# ArduinoPCB_test.net
KiCad netlist of a schematic drawn in EAGLE
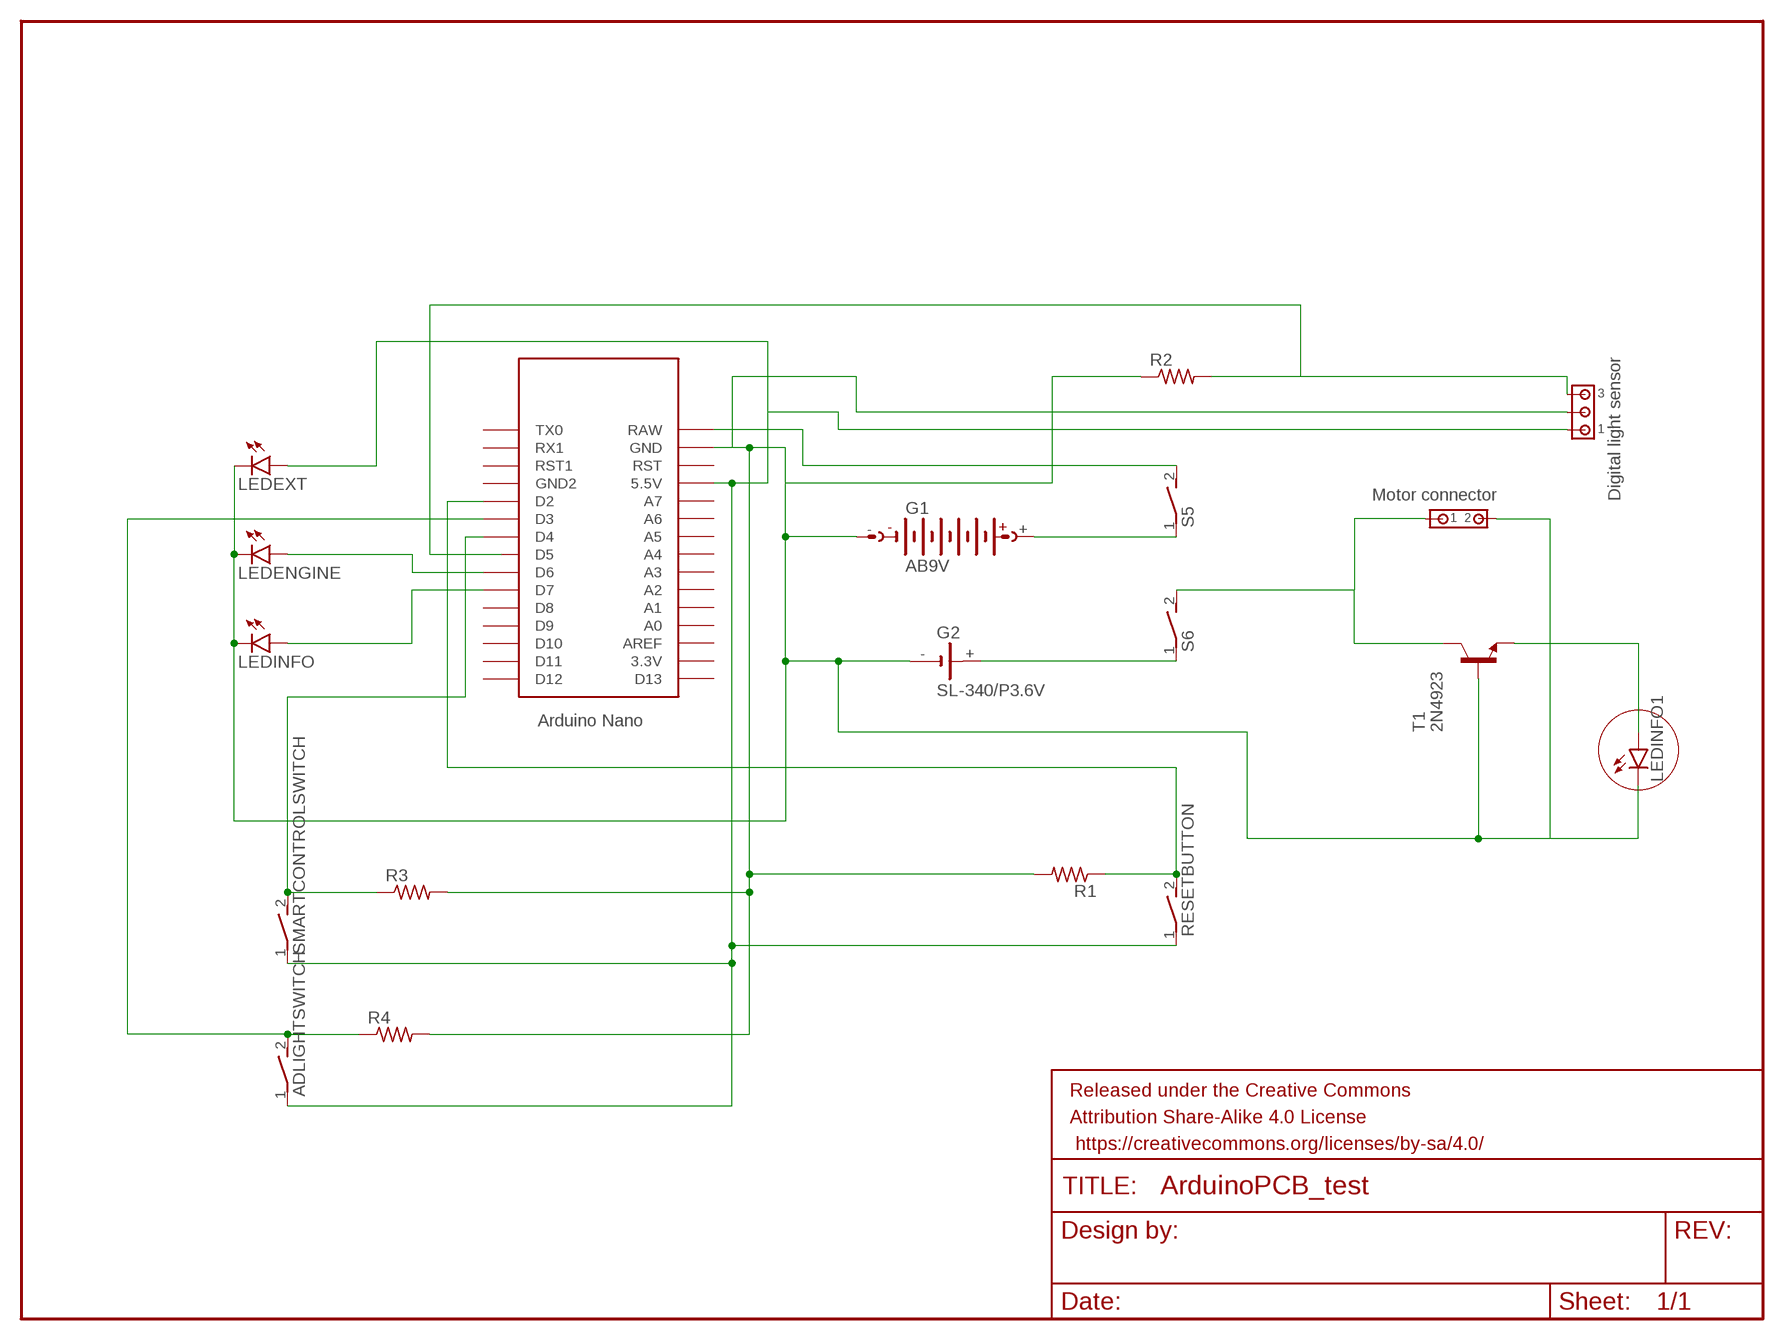
[diagram p0: schematic, sheet 1]

(export (version "E")
  (design (tool "Eeschema 10.0.6"))
  (components
    (comp (ref "ADLIGHTSWITCH")
      (value "DS01E")
      (footprint "eagle-import:DS-01")
      (libsource (lib "eagle-import") (part "DS01E"))
    )
    (comp (ref "FRAME1")
      (value "FRAME-LETTER")
      (footprint "eagle-import:CREATIVE_COMMONS")
      (libsource (lib "eagle-import") (part "FRAME-LETTER"))
    )
    (comp (ref "G1")
      (value "AB9V")
      (footprint "eagle-import:AB9V")
      (libsource (lib "eagle-import") (part "AB9V"))
    )
    (comp (ref "G2")
      (value "SL-340/P3.6V")
      (footprint "eagle-import:SL-340_P3.6V")
      (libsource (lib "eagle-import") (part "SL-340/P3.6V"))
    )
    (comp (ref "J1")
      (value "794681-2")
      (footprint "eagle-import:794681-2")
      (fields (field (name "POPULARITY") "0") (field (name "POPULARITY_1") "Motor connector"))
      (libsource (lib "eagle-import") (part "794681-2"))
    )
    (comp (ref "J2")
      (value "1445055-3")
      (footprint "eagle-import:1445055-3")
      (fields (field (name "POPULARITY") "0") (field (name "POPULARITY_1") "Digital light sensor"))
      (libsource (lib "eagle-import") (part "1445055-3"))
    )
    (comp (ref "LEDENGINE")
      (value "LED3MM")
      (footprint "eagle-import:LED3MM")
      (libsource (lib "eagle-import") (part "LED3MM"))
    )
    (comp (ref "LEDEXT")
      (value "LED3MM")
      (footprint "eagle-import:LED3MM")
      (libsource (lib "eagle-import") (part "LED3MM"))
    )
    (comp (ref "LEDINFO")
      (value "LED3MM")
      (footprint "eagle-import:LED3MM")
      (libsource (lib "eagle-import") (part "LED3MM"))
    )
    (comp (ref "LEDINFO1")
      (value "LED3MM")
      (footprint "eagle-import:LED3MM")
      (libsource (lib "eagle-import") (part "LED3MM"))
    )
    (comp (ref "R1")
      (value "R-US_0309/12")
      (footprint "eagle-import:0309_12")
      (libsource (lib "eagle-import") (part "R-US_0309/12"))
    )
    (comp (ref "R2")
      (value "R-US_0309/12")
      (footprint "eagle-import:0309_12")
      (libsource (lib "eagle-import") (part "R-US_0309/12"))
    )
    (comp (ref "R3")
      (value "R-US_0309/12")
      (footprint "eagle-import:0309_12")
      (libsource (lib "eagle-import") (part "R-US_0309/12"))
    )
    (comp (ref "R4")
      (value "R-US_0309/12")
      (footprint "eagle-import:0309_12")
      (libsource (lib "eagle-import") (part "R-US_0309/12"))
    )
    (comp (ref "RESETBUTTON")
      (value "DS01E")
      (footprint "eagle-import:DS-01")
      (libsource (lib "eagle-import") (part "DS01E"))
    )
    (comp (ref "S5")
      (value "DS01E")
      (footprint "eagle-import:DS-01")
      (libsource (lib "eagle-import") (part "DS01E"))
    )
    (comp (ref "S6")
      (value "DS01E")
      (footprint "eagle-import:DS-01")
      (libsource (lib "eagle-import") (part "DS01E"))
    )
    (comp (ref "SMARTCONTROLSWITCH")
      (value "DS01E")
      (footprint "eagle-import:DS-01")
      (libsource (lib "eagle-import") (part "DS01E"))
    )
    (comp (ref "T1")
      (value "2N4923")
      (footprint "eagle-import:TO126")
      (libsource (lib "eagle-import") (part "2N4923"))
    )
    (comp (ref "U$1")
      (value "NANO")
      (footprint "eagle-import:NANO")
      (libsource (lib "eagle-import") (part "NANO"))
    )
  )
  (nets
    (net (code "1") (name "Net-(ADLIGHTSWITCH-Pad2)") (class "Default")
      (node (ref "ADLIGHTSWITCH") (pin "2") (pinfunction "2_2") (pintype "passive"))
      (node (ref "R4") (pin "1") (pinfunction "1_1") (pintype "passive"))
      (node (ref "U$1") (pin "D3") (pinfunction "D3_D3") (pintype "bidirectional"))
    )
    (net (code "2") (name "Net-(G1-Pad+)") (class "Default")
      (node (ref "G1") (pin "+") (pinfunction "+_+") (pintype "passive"))
      (node (ref "S5") (pin "1") (pinfunction "1_1") (pintype "passive"))
    )
    (net (code "3") (name "Net-(G2-Pad+)") (class "Default")
      (node (ref "G2") (pin "+") (pinfunction "+_+") (pintype "passive"))
      (node (ref "S6") (pin "1") (pinfunction "1_1") (pintype "passive"))
    )
    (net (code "4") (name "Net-(J2-Pad3)") (class "Default")
      (node (ref "J2") (pin "3") (pinfunction "3_3") (pintype "passive"))
      (node (ref "R2") (pin "2") (pinfunction "2_2") (pintype "passive"))
    )
    (net (code "5") (name "Net-(LEDENGINE-C)") (class "Default")
      (node (ref "G1") (pin "-") (pinfunction "-_-") (pintype "passive"))
      (node (ref "G2") (pin "-") (pinfunction "-_-") (pintype "passive"))
      (node (ref "J1") (pin "2") (pinfunction "2_2") (pintype "passive"))
      (node (ref "J2") (pin "2") (pinfunction "2_2") (pintype "passive"))
      (node (ref "LEDENGINE") (pin "K") (pinfunction "C_K") (pintype "passive"))
      (node (ref "LEDEXT") (pin "K") (pinfunction "C_K") (pintype "passive"))
      (node (ref "LEDINFO") (pin "K") (pinfunction "C_K") (pintype "passive"))
      (node (ref "LEDINFO1") (pin "K") (pinfunction "C_K") (pintype "passive"))
      (node (ref "R1") (pin "2") (pinfunction "2_2") (pintype "passive"))
      (node (ref "R2") (pin "1") (pinfunction "1_1") (pintype "passive"))
      (node (ref "R3") (pin "2") (pinfunction "2_2") (pintype "passive"))
      (node (ref "R4") (pin "2") (pinfunction "2_2") (pintype "passive"))
      (node (ref "T1") (pin "3") (pinfunction "B_3") (pintype "passive"))
      (node (ref "U$1") (pin "GND") (pinfunction "GND_GND") (pintype "bidirectional"))
    )
    (net (code "6") (name "Net-(LEDENGINE-PadA)") (class "Default")
      (node (ref "LEDENGINE") (pin "A") (pinfunction "A_A") (pintype "passive"))
      (node (ref "U$1") (pin "D6") (pinfunction "D6_D6") (pintype "bidirectional"))
    )
    (net (code "7") (name "Net-(LEDINFO-PadA)") (class "Default")
      (node (ref "LEDINFO") (pin "A") (pinfunction "A_A") (pintype "passive"))
      (node (ref "U$1") (pin "D7") (pinfunction "D7_D7") (pintype "bidirectional"))
    )
    (net (code "8") (name "Net-(R1-Pad1)") (class "Default")
      (node (ref "R1") (pin "1") (pinfunction "1_1") (pintype "passive"))
      (node (ref "RESETBUTTON") (pin "2") (pinfunction "2_2") (pintype "passive"))
      (node (ref "U$1") (pin "D2") (pinfunction "D2_D2") (pintype "bidirectional"))
    )
    (net (code "9") (name "Net-(R3-Pad1)") (class "Default")
      (node (ref "R3") (pin "1") (pinfunction "1_1") (pintype "passive"))
      (node (ref "SMARTCONTROLSWITCH") (pin "2") (pinfunction "2_2") (pintype "passive"))
      (node (ref "U$1") (pin "D4") (pinfunction "D4_D4") (pintype "bidirectional"))
    )
    (net (code "10") (name "Net-(S5-Pad2)") (class "Default")
      (node (ref "S5") (pin "2") (pinfunction "2_2") (pintype "passive"))
      (node (ref "U$1") (pin "RAW") (pinfunction "RAW_RAW") (pintype "bidirectional"))
    )
    (net (code "11") (name "Net-(T1-C)") (class "Default")
      (node (ref "J1") (pin "1") (pinfunction "1_1") (pintype "passive"))
      (node (ref "S6") (pin "2") (pinfunction "2_2") (pintype "passive"))
      (node (ref "T1") (pin "2") (pinfunction "C_2") (pintype "passive"))
    )
    (net (code "12") (name "Net-(T1-E)") (class "Default")
      (node (ref "LEDINFO1") (pin "A") (pinfunction "A_A") (pintype "passive"))
      (node (ref "T1") (pin "1") (pinfunction "E_1") (pintype "passive"))
    )
    (net (code "13") (name "Net-(U$1-5.5V)") (class "Default")
      (node (ref "ADLIGHTSWITCH") (pin "1") (pinfunction "1_1") (pintype "passive"))
      (node (ref "J2") (pin "1") (pinfunction "1_1") (pintype "passive"))
      (node (ref "LEDEXT") (pin "A") (pinfunction "A_A") (pintype "passive"))
      (node (ref "RESETBUTTON") (pin "1") (pinfunction "1_1") (pintype "passive"))
      (node (ref "SMARTCONTROLSWITCH") (pin "1") (pinfunction "1_1") (pintype "passive"))
      (node (ref "U$1") (pin "5V") (pinfunction "5.5V_5V") (pintype "bidirectional"))
    )
    (net (code "14") (name "unconnected-(U$1-GND2-PadGND1)") (class "Default")
      (node (ref "U$1") (pin "GND1") (pinfunction "GND2_GND1") (pintype "bidirectional"))
    )
    (net (code "15") (name "unconnected-(U$1-Pad3.3V)") (class "Default")
      (node (ref "U$1") (pin "3.3V") (pinfunction "3.3V_3.3V") (pintype "bidirectional"))
    )
    (net (code "16") (name "unconnected-(U$1-PadA0)") (class "Default")
      (node (ref "U$1") (pin "A0") (pinfunction "A0_A0") (pintype "bidirectional"))
    )
    (net (code "17") (name "unconnected-(U$1-PadA1)") (class "Default")
      (node (ref "U$1") (pin "A1") (pinfunction "A1_A1") (pintype "bidirectional"))
    )
    (net (code "18") (name "unconnected-(U$1-PadA2)") (class "Default")
      (node (ref "U$1") (pin "A2") (pinfunction "A2_A2") (pintype "bidirectional"))
    )
    (net (code "19") (name "unconnected-(U$1-PadA3)") (class "Default")
      (node (ref "U$1") (pin "A3") (pinfunction "A3_A3") (pintype "bidirectional"))
    )
    (net (code "20") (name "unconnected-(U$1-PadA4)") (class "Default")
      (node (ref "U$1") (pin "A4") (pinfunction "A4_A4") (pintype "bidirectional"))
    )
    (net (code "21") (name "unconnected-(U$1-PadA5)") (class "Default")
      (node (ref "U$1") (pin "A5") (pinfunction "A5_A5") (pintype "bidirectional"))
    )
    (net (code "22") (name "unconnected-(U$1-PadA6)") (class "Default")
      (node (ref "U$1") (pin "A6") (pinfunction "A6_A6") (pintype "bidirectional"))
    )
    (net (code "23") (name "unconnected-(U$1-PadA7)") (class "Default")
      (node (ref "U$1") (pin "A7") (pinfunction "A7_A7") (pintype "bidirectional"))
    )
    (net (code "24") (name "unconnected-(U$1-PadAREF)") (class "Default")
      (node (ref "U$1") (pin "AREF") (pinfunction "AREF_AREF") (pintype "bidirectional"))
    )
    (net (code "25") (name "unconnected-(U$1-PadD5)") (class "Default")
      (node (ref "U$1") (pin "D5") (pinfunction "D5_D5") (pintype "bidirectional"))
    )
    (net (code "26") (name "unconnected-(U$1-PadD8)") (class "Default")
      (node (ref "U$1") (pin "D8") (pinfunction "D8_D8") (pintype "bidirectional"))
    )
    (net (code "27") (name "unconnected-(U$1-PadD9)") (class "Default")
      (node (ref "U$1") (pin "D9") (pinfunction "D9_D9") (pintype "bidirectional"))
    )
    (net (code "28") (name "unconnected-(U$1-PadD10)") (class "Default")
      (node (ref "U$1") (pin "D10") (pinfunction "D10_D10") (pintype "bidirectional"))
    )
    (net (code "29") (name "unconnected-(U$1-PadD11)") (class "Default")
      (node (ref "U$1") (pin "D11") (pinfunction "D11_D11") (pintype "bidirectional"))
    )
    (net (code "30") (name "unconnected-(U$1-PadD12)") (class "Default")
      (node (ref "U$1") (pin "D12") (pinfunction "D12_D12") (pintype "bidirectional"))
    )
    (net (code "31") (name "unconnected-(U$1-PadD13)") (class "Default")
      (node (ref "U$1") (pin "D13") (pinfunction "D13_D13") (pintype "bidirectional"))
    )
    (net (code "32") (name "unconnected-(U$1-PadICSP1)") (class "Default")
      (node (ref "U$1") (pin "ICSP1") (pinfunction "ICSP1_ICSP1") (pintype "bidirectional"))
    )
    (net (code "33") (name "unconnected-(U$1-PadICSP2)") (class "Default")
      (node (ref "U$1") (pin "ICSP2") (pinfunction "ICSP2_ICSP2") (pintype "bidirectional"))
    )
    (net (code "34") (name "unconnected-(U$1-PadICSP3)") (class "Default")
      (node (ref "U$1") (pin "ICSP3") (pinfunction "ICSP3_ICSP3") (pintype "bidirectional"))
    )
    (net (code "35") (name "unconnected-(U$1-PadICSP4)") (class "Default")
      (node (ref "U$1") (pin "ICSP4") (pinfunction "ICSP4_ICSP4") (pintype "bidirectional"))
    )
    (net (code "36") (name "unconnected-(U$1-PadICSP5)") (class "Default")
      (node (ref "U$1") (pin "ICSP5") (pinfunction "ICSP5_ICSP5") (pintype "bidirectional"))
    )
    (net (code "37") (name "unconnected-(U$1-PadICSP6)") (class "Default")
      (node (ref "U$1") (pin "ICSP6") (pinfunction "ICSP6_ICSP6") (pintype "bidirectional"))
    )
    (net (code "38") (name "unconnected-(U$1-PadRST)") (class "Default")
      (node (ref "U$1") (pin "RST") (pinfunction "RST_RST") (pintype "bidirectional"))
    )
    (net (code "39") (name "unconnected-(U$1-PadRST1)") (class "Default")
      (node (ref "U$1") (pin "RST1") (pinfunction "RST1_RST1") (pintype "bidirectional"))
    )
    (net (code "40") (name "unconnected-(U$1-PadRX1)") (class "Default")
      (node (ref "U$1") (pin "RX1") (pinfunction "RX1_RX1") (pintype "bidirectional"))
    )
    (net (code "41") (name "unconnected-(U$1-PadTX0)") (class "Default")
      (node (ref "U$1") (pin "TX0") (pinfunction "TX0_TX0") (pintype "bidirectional"))
    )
  )
)
